# LPCB278_-_POWER.net
KiCad netlist of a schematic drawn in Altium Designer
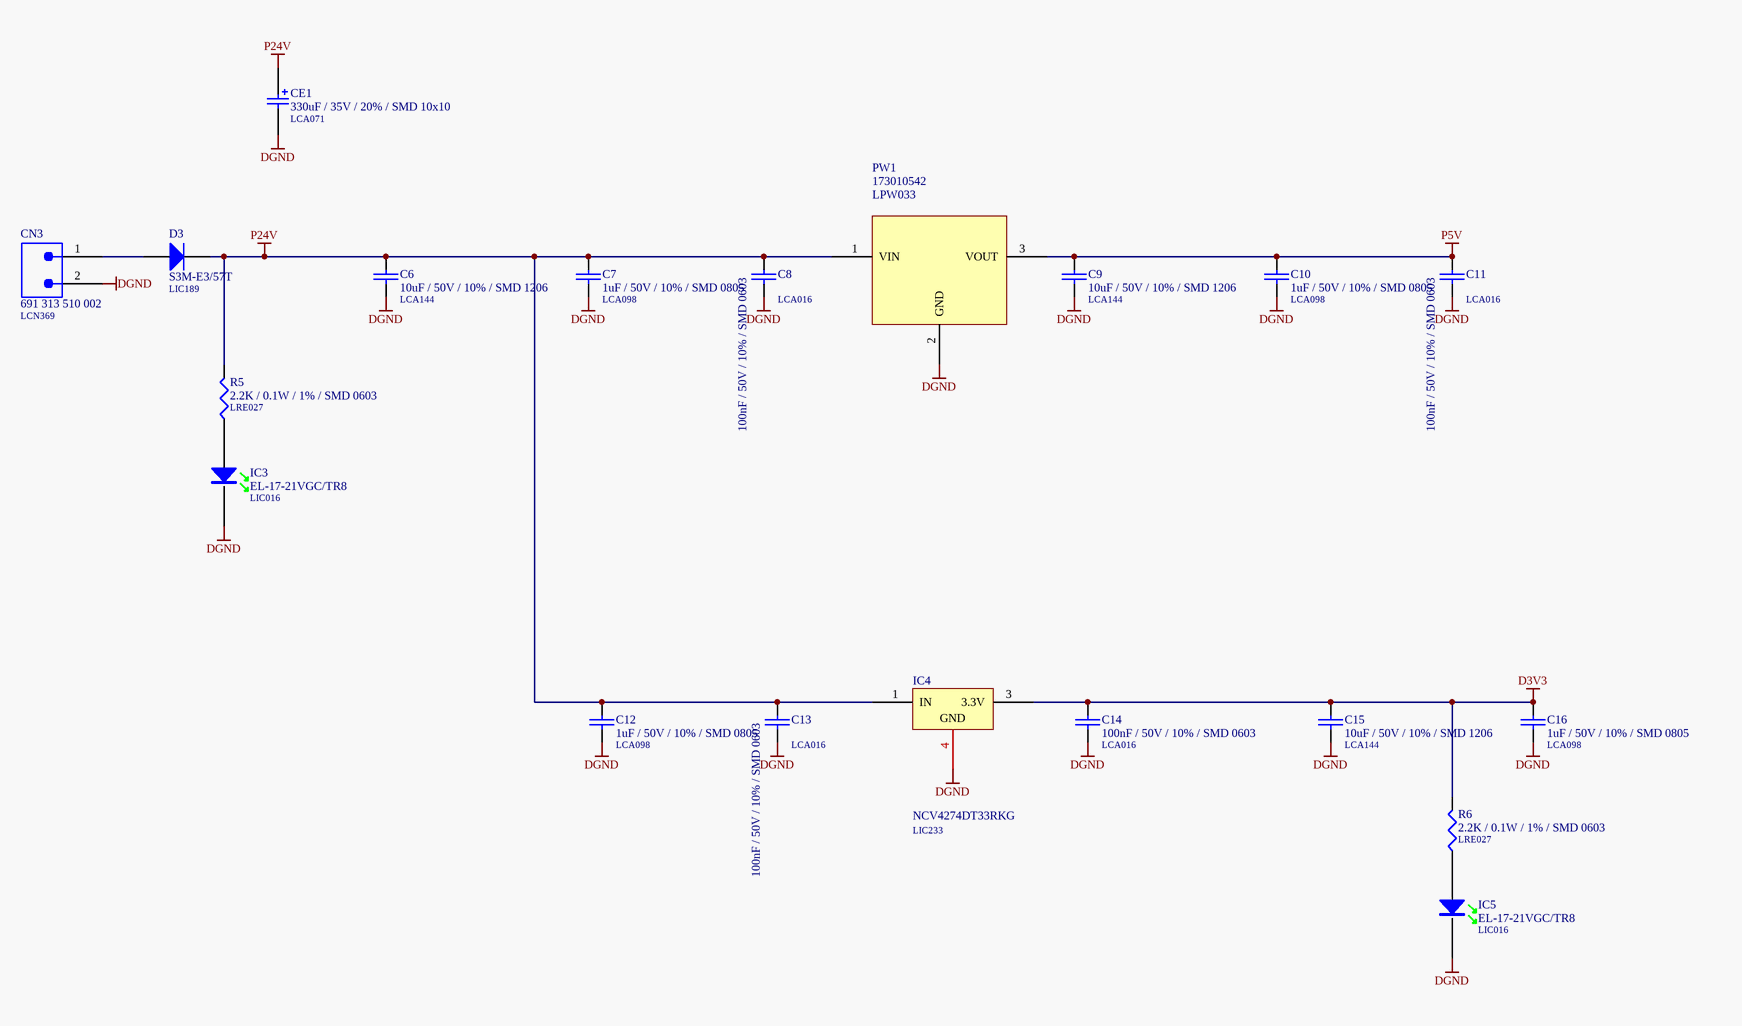
[diagram p0: LPCB278 - POWER.SchDoc]

(export (version "E")
  (design (tool "Eeschema 10.0.6"))
  (components
    (comp (ref "C6")
      (value "10uF / 50V / 10% / SMD 1206")
      (footprint "LFP043__CC3216-1206")
      (description "Capacitor, Ceramic Chip, 10uF, 50V, X5R, 10%, SMD 1206 [LCA144]")
      (fields (field (name "LDL_NUMBER") "LCA144"))
      (libsource (lib "LDL_Capacitors") (part "10uF / 50V / 10% / SMD 1206"))
    )
    (comp (ref "C7")
      (value "1uF / 50V / 10% / SMD 0805")
      (footprint "LFP010__CC2012-0805-IPC7351_B")
      (description "Capacitor, Ceramic Chip, 1uF, 50V, SMD 0805 [LCA098]")
      (fields (field (name "LDL_NUMBER") "LCA098"))
      (libsource (lib "LDL_Capacitors") (part "1uF / 50V / 10% / SMD 0805"))
    )
    (comp (ref "C8")
      (value "100nF / 50V / 10% / SMD 0603")
      (footprint "LFP011__CC1608-0603-IPC7351_B")
      (description "Capacitor, Ceramic Chip, 100nF (0.1uF), 50V, 5%, SMD 0603 [LCA016]")
      (fields (field (name "LDL_NUMBER") "LCA016"))
      (libsource (lib "LDL_Capacitors") (part "100nF / 50V / 10% / SMD 0603"))
    )
    (comp (ref "C9")
      (value "10uF / 50V / 10% / SMD 1206")
      (footprint "LFP043__CC3216-1206")
      (description "Capacitor, Ceramic Chip, 10uF, 50V, X5R, 10%, SMD 1206 [LCA144]")
      (fields (field (name "LDL_NUMBER") "LCA144"))
      (libsource (lib "LDL_Capacitors") (part "10uF / 50V / 10% / SMD 1206"))
    )
    (comp (ref "C10")
      (value "1uF / 50V / 10% / SMD 0805")
      (footprint "LFP010__CC2012-0805-IPC7351_B")
      (description "Capacitor, Ceramic Chip, 1uF, 50V, SMD 0805 [LCA098]")
      (fields (field (name "LDL_NUMBER") "LCA098"))
      (libsource (lib "LDL_Capacitors") (part "1uF / 50V / 10% / SMD 0805"))
    )
    (comp (ref "C11")
      (value "100nF / 50V / 10% / SMD 0603")
      (footprint "LFP011__CC1608-0603-IPC7351_B")
      (description "Capacitor, Ceramic Chip, 100nF (0.1uF), 50V, 5%, SMD 0603 [LCA016]")
      (fields (field (name "LDL_NUMBER") "LCA016"))
      (libsource (lib "LDL_Capacitors") (part "100nF / 50V / 10% / SMD 0603"))
    )
    (comp (ref "C12")
      (value "1uF / 50V / 10% / SMD 0805")
      (footprint "LFP010__CC2012-0805-IPC7351_B")
      (description "Capacitor, Ceramic Chip, 1uF, 50V, SMD 0805 [LCA098]")
      (fields (field (name "LDL_NUMBER") "LCA098"))
      (libsource (lib "LDL_Capacitors") (part "1uF / 50V / 10% / SMD 0805"))
    )
    (comp (ref "C13")
      (value "100nF / 50V / 10% / SMD 0603")
      (footprint "LFP011__CC1608-0603-IPC7351_B")
      (description "Capacitor, Ceramic Chip, 100nF (0.1uF), 50V, 5%, SMD 0603 [LCA016]")
      (fields (field (name "LDL_NUMBER") "LCA016"))
      (libsource (lib "LDL_Capacitors") (part "100nF / 50V / 10% / SMD 0603"))
    )
    (comp (ref "C14")
      (value "100nF / 50V / 10% / SMD 0603")
      (footprint "LFP011__CC1608-0603-IPC7351_B")
      (description "Capacitor, Ceramic Chip, 100nF (0.1uF), 50V, 5%, SMD 0603 [LCA016]")
      (fields (field (name "LDL_NUMBER") "LCA016"))
      (libsource (lib "LDL_Capacitors") (part "100nF / 50V / 10% / SMD 0603"))
    )
    (comp (ref "C15")
      (value "10uF / 50V / 10% / SMD 1206")
      (footprint "LFP043__CC3216-1206")
      (description "Capacitor, Ceramic Chip, 10uF, 50V, X5R, 10%, SMD 1206 [LCA144]")
      (fields (field (name "LDL_NUMBER") "LCA144"))
      (libsource (lib "LDL_Capacitors") (part "10uF / 50V / 10% / SMD 1206"))
    )
    (comp (ref "C16")
      (value "1uF / 50V / 10% / SMD 0805")
      (footprint "LFP010__CC2012-0805-IPC7351_B")
      (description "Capacitor, Ceramic Chip, 1uF, 50V, SMD 0805 [LCA098]")
      (fields (field (name "LDL_NUMBER") "LCA098"))
      (libsource (lib "LDL_Capacitors") (part "1uF / 50V / 10% / SMD 0805"))
    )
    (comp (ref "CE1")
      (value "330uF / 35V / 20% / SMD 10x10")
      (footprint "LFP041__NICHICON_WT_10X10")
      (description "Capacitor, Aluminum Electrolytic, 330uF, 35V, 20%, SMD (10mm x 10mm) [LCA071]")
      (fields (field (name "LDL_NUMBER") "LCA071"))
      (libsource (lib "LDL_Capacitors") (part "330uF / 35V / 20% / SMD 10x10"))
    )
    (comp (ref "CN3")
      (value "691 313 510 002")
      (footprint "691 313 510 002")
      (description "Connector, Pluggable Terminal Block, 5.08mm, 2 Way, PTH")
      (fields (field (name "LDL_NUMBER") "LCN369"))
      (libsource (lib "LDL_Connectors") (part "691 313 510 002"))
    )
    (comp (ref "D3")
      (value "S3M-E3/57T")
      (footprint "LFP040__DO-214AB")
      (description "Diode, General Purpose Rectifier, 3A, 200V, SMD DO-214AB [LIC189]")
      (fields (field (name "LDL_NUMBER") "LIC189"))
      (libsource (lib "LDL_Semiconductors") (part "S3M-E3/57T"))
    )
    (comp (ref "IC3")
      (value "EL-17-21VGC/TR8")
      (footprint "CR2012-0805-LED")
      (description "LED, SMD, 0805 Green [LIC016]")
      (fields (field (name "LDL_NUMBER") "LIC016"))
      (libsource (lib "LDL_Semiconductors") (part "EL-17-21VGC/TR8"))
    )
    (comp (ref "IC4")
      (value "NCV4274DT33RKG")
      (footprint "LFP019__369A-13")
      (description "IC, Voltage Regulator, 400mA, 3.3V LDO, SMD DPAK [LIC233]")
      (fields (field (name "LDL_NUMBER") "LIC233"))
      (libsource (lib "LDL_Semiconductors") (part "NCV4274DT33RKG"))
    )
    (comp (ref "IC5")
      (value "EL-17-21VGC/TR8")
      (footprint "CR2012-0805-LED")
      (description "LED, SMD, 0805 Green [LIC016]")
      (fields (field (name "LDL_NUMBER") "LIC016"))
      (libsource (lib "LDL_Semiconductors") (part "EL-17-21VGC/TR8"))
    )
    (comp (ref "PW1")
      (value "173010542")
      (footprint "173010542")
      (fields (field (name "LDL_NUMBER") "LPW033"))
      (libsource (lib "LDL_Power") (part "173010542"))
    )
    (comp (ref "R5")
      (value "2.2K / 0.1W / 1% / SMD 0603")
      (footprint "LFP020__CR1608-0603-IPC7351_B")
      (description "Resistor, Ceramic Chip, 2.2K, 0.1W, 1%, SMD 0603 [LRE027]")
      (fields (field (name "LDL_NUMBER") "LRE027"))
      (libsource (lib "LDL_Resistors") (part "2.2K / 0.1W / 1% / SMD 0603"))
    )
    (comp (ref "R6")
      (value "2.2K / 0.1W / 1% / SMD 0603")
      (footprint "LFP020__CR1608-0603-IPC7351_B")
      (description "Resistor, Ceramic Chip, 2.2K, 0.1W, 1%, SMD 0603 [LRE027]")
      (fields (field (name "LDL_NUMBER") "LRE027"))
      (libsource (lib "LDL_Resistors") (part "2.2K / 0.1W / 1% / SMD 0603"))
    )
  )
  (nets
    (net (code "1") (name "D3V3") (class "Default")
      (node (ref "C14") (pin "1") (pintype "passive"))
      (node (ref "C15") (pin "1") (pintype "passive"))
      (node (ref "C16") (pin "1") (pintype "passive"))
      (node (ref "IC4") (pin "3") (pinfunction "3.3V_3") (pintype "power_in"))
      (node (ref "R6") (pin "2") (pintype "passive"))
    )
    (net (code "2") (name "DGND") (class "Default")
      (node (ref "C10") (pin "2") (pintype "passive"))
      (node (ref "C11") (pin "2") (pintype "passive"))
      (node (ref "C12") (pin "2") (pintype "passive"))
      (node (ref "C13") (pin "2") (pintype "passive"))
      (node (ref "C14") (pin "2") (pintype "passive"))
      (node (ref "C15") (pin "2") (pintype "passive"))
      (node (ref "C16") (pin "2") (pintype "passive"))
      (node (ref "C6") (pin "2") (pintype "passive"))
      (node (ref "C7") (pin "2") (pintype "passive"))
      (node (ref "C8") (pin "2") (pintype "passive"))
      (node (ref "C9") (pin "2") (pintype "passive"))
      (node (ref "CE1") (pin "2") (pinfunction "2_2") (pintype "passive"))
      (node (ref "CN3") (pin "2") (pinfunction "2_2") (pintype "passive"))
      (node (ref "IC3") (pin "K") (pintype "passive"))
      (node (ref "IC4") (pin "4") (pinfunction "GND_4") (pintype "power_in"))
      (node (ref "IC5") (pin "K") (pintype "passive"))
      (node (ref "PW1") (pin "2") (pinfunction "GND_2") (pintype "passive"))
    )
    (net (code "3") (name "Net-(D3-A)") (class "Default")
      (node (ref "CN3") (pin "1") (pinfunction "1_1") (pintype "passive"))
      (node (ref "D3") (pin "2") (pinfunction "A_2") (pintype "passive"))
    )
    (net (code "4") (name "Net-(IC3-PadA)") (class "Default")
      (node (ref "IC3") (pin "A") (pintype "passive"))
      (node (ref "R5") (pin "1") (pintype "passive"))
    )
    (net (code "5") (name "Net-(IC5-PadA)") (class "Default")
      (node (ref "IC5") (pin "A") (pintype "passive"))
      (node (ref "R6") (pin "1") (pintype "passive"))
    )
    (net (code "6") (name "P5V") (class "Default")
      (node (ref "C10") (pin "1") (pintype "passive"))
      (node (ref "C11") (pin "1") (pintype "passive"))
      (node (ref "C9") (pin "1") (pintype "passive"))
      (node (ref "PW1") (pin "3") (pinfunction "VOUT_3") (pintype "passive"))
    )
    (net (code "7") (name "P24V") (class "Default")
      (node (ref "C12") (pin "1") (pintype "passive"))
      (node (ref "C13") (pin "1") (pintype "passive"))
      (node (ref "C6") (pin "1") (pintype "passive"))
      (node (ref "C7") (pin "1") (pintype "passive"))
      (node (ref "C8") (pin "1") (pintype "passive"))
      (node (ref "CE1") (pin "1") (pinfunction "1_1") (pintype "passive"))
      (node (ref "D3") (pin "1") (pinfunction "K_1") (pintype "passive"))
      (node (ref "IC4") (pin "1") (pinfunction "IN_1") (pintype "power_in"))
      (node (ref "PW1") (pin "1") (pinfunction "VIN_1") (pintype "passive"))
      (node (ref "R5") (pin "2") (pintype "passive"))
    )
  )
)
